# 2_1.net
KiCad netlist of a schematic drawn in EasyEDA Pro
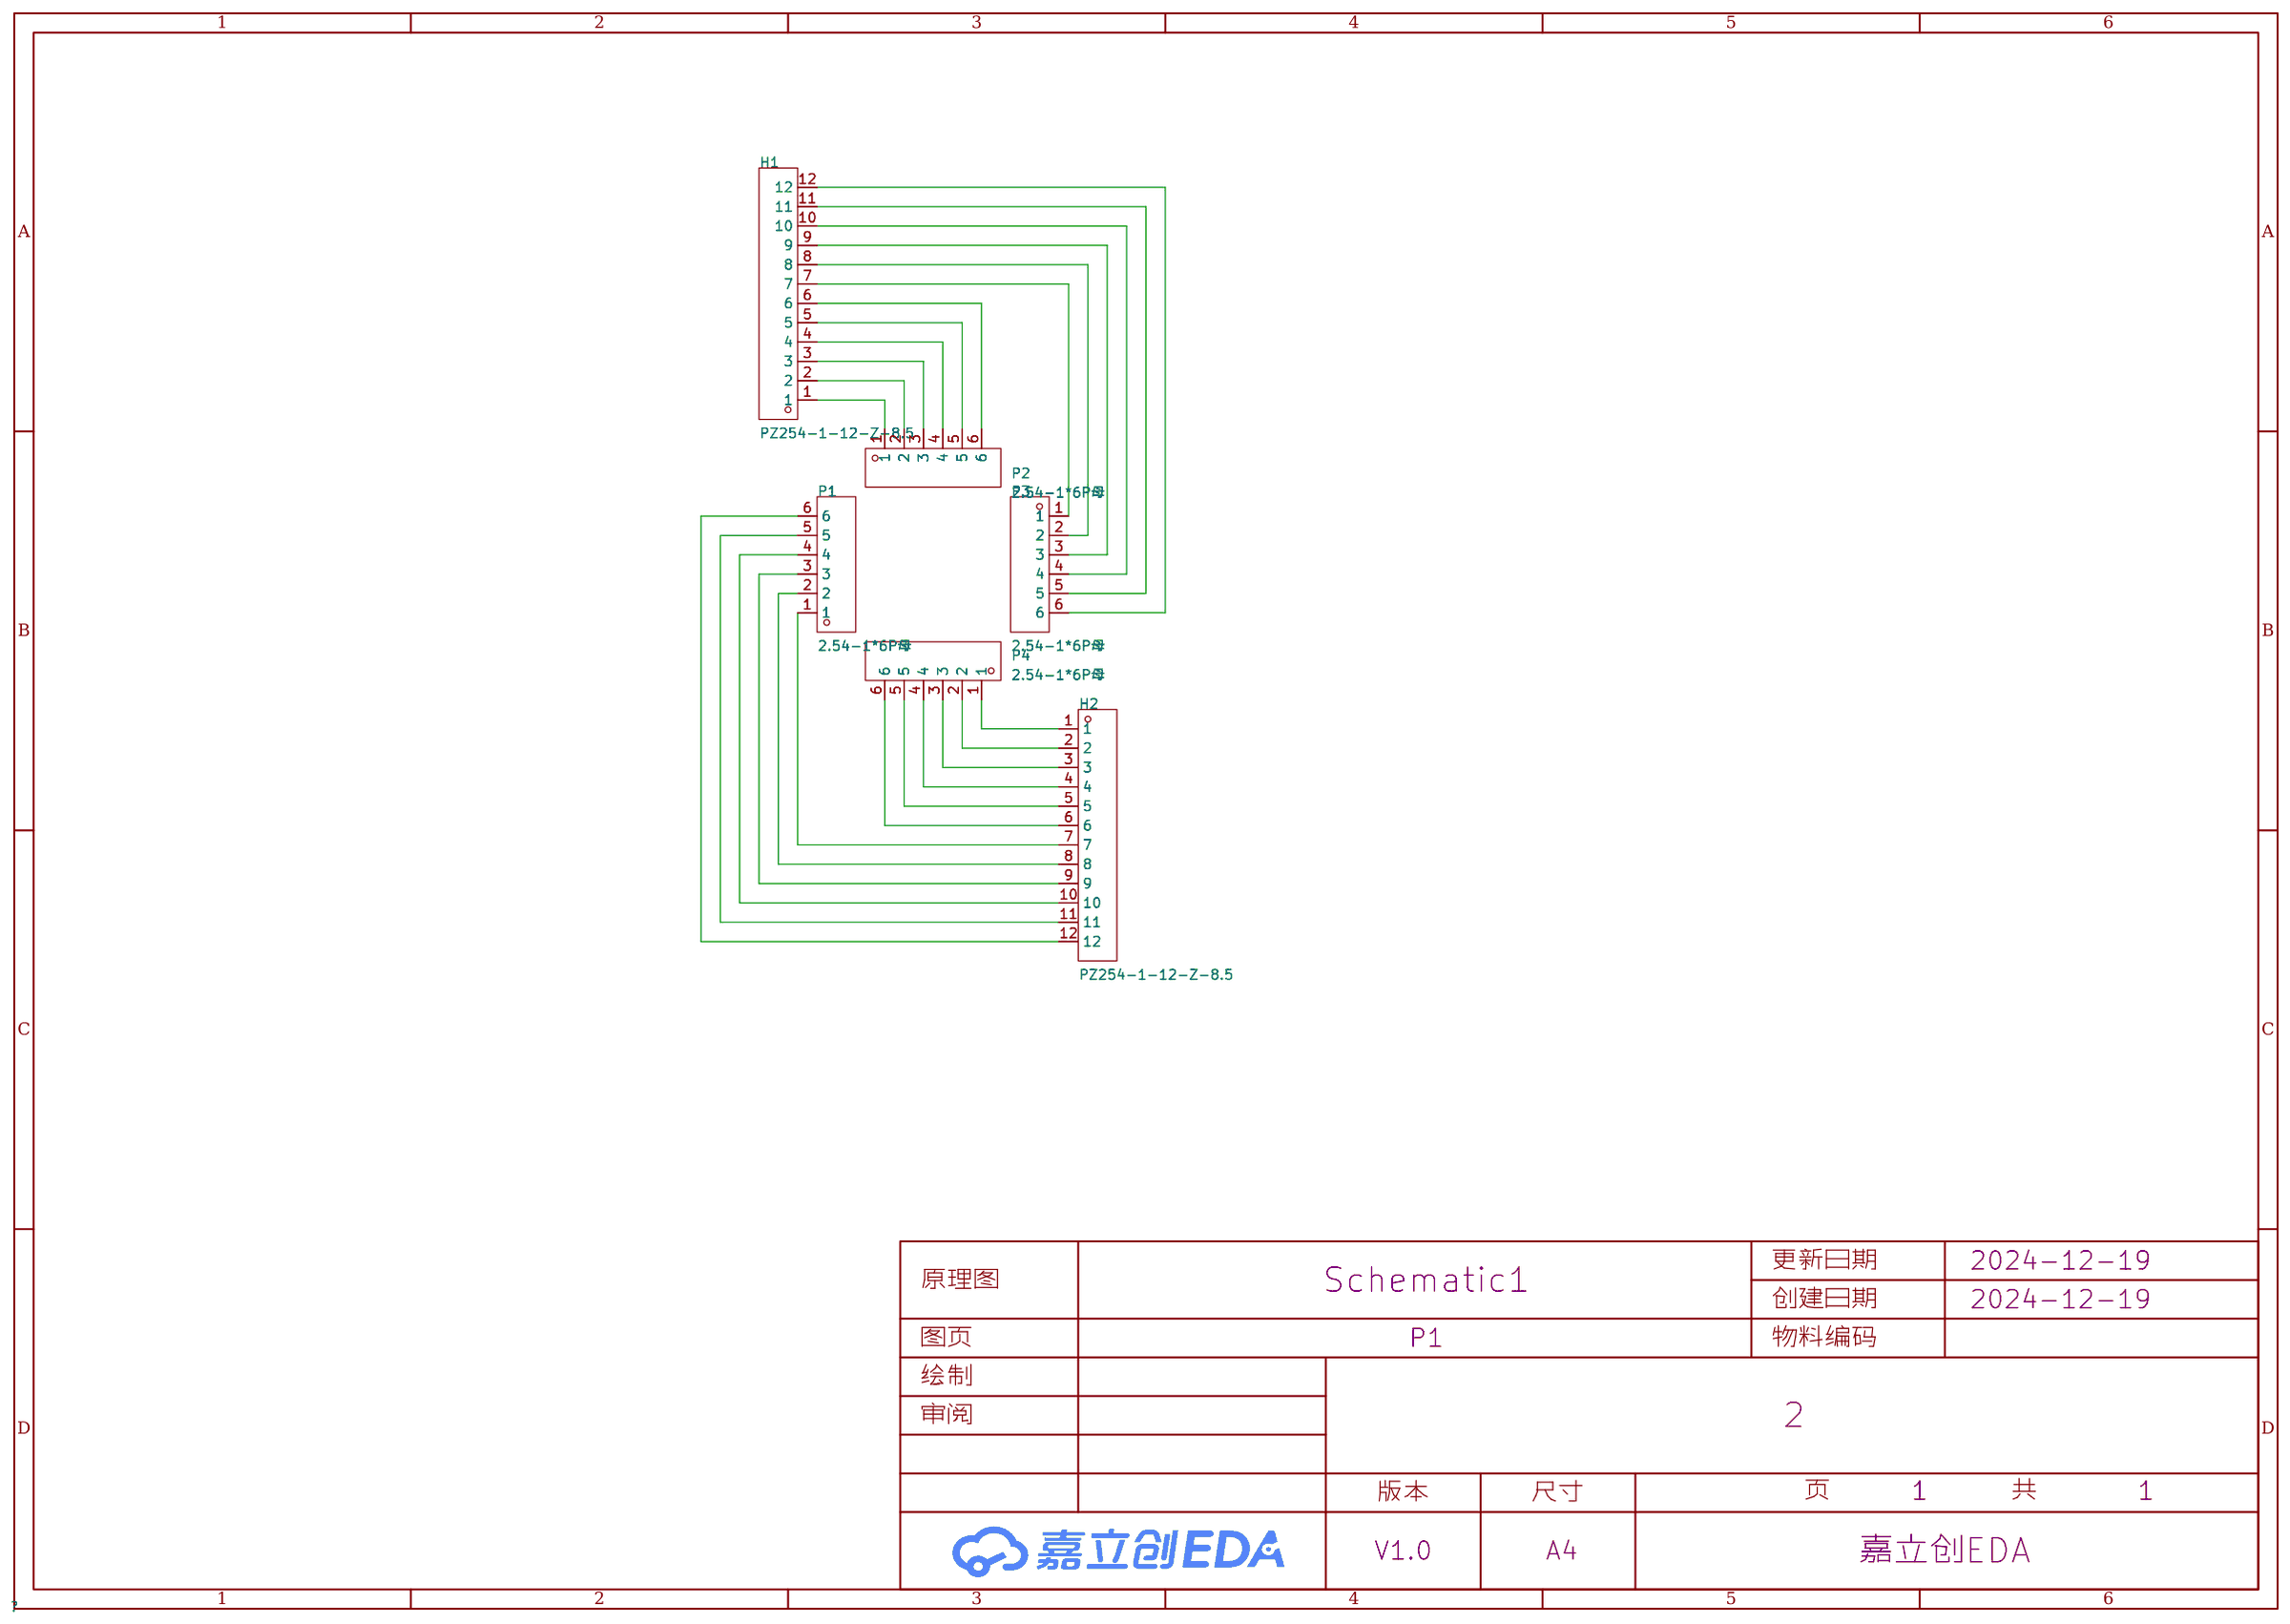
[diagram p0: schematic sheet]

(export (version "E")
  (design (tool "Eeschema 10.0.6"))
  (components
    (comp (ref "H1")
      (value "PZ254-1-12-Z-8.5")
      (footprint "easyedapro:HDR-TH_12P-P2.54-V-M")
      (fields (field (name "Manufacturer") "HCTL(华灿天禄)"))
      (libsource (lib "easyedapro") (part "PZ254-1-12-Z-8.5"))
    )
    (comp (ref "H2")
      (value "PZ254-1-12-Z-8.5")
      (footprint "easyedapro:HDR-TH_12P-P2.54-V-M")
      (fields (field (name "Manufacturer") "HCTL(华灿天禄)"))
      (libsource (lib "easyedapro") (part "PZ254-1-12-Z-8.5"))
    )
    (comp (ref "P1")
      (value "2.54-1*6P母")
      (footprint "easyedapro:HDR-TH_6P-P2.54-V-F")
      (description "插孔结构:1x6P;间距:2.54mm;行距:-;安装类型:直插;排数:单排;总孔位数:6P;塑高:-;触头材质:-;触头镀层:-;")
      (fields (field (name "Manufacturer") "BOOMELE(博穆精密)"))
      (libsource (lib "easyedapro") (part "Header-Female-2.54_1x6"))
    )
    (comp (ref "P2")
      (value "2.54-1*6P母")
      (footprint "easyedapro:HDR-TH_6P-P2.54-V-F")
      (description "插孔结构:1x6P;间距:2.54mm;行距:-;安装类型:直插;排数:单排;总孔位数:6P;塑高:-;触头材质:-;触头镀层:-;")
      (fields (field (name "Manufacturer") "BOOMELE(博穆精密)"))
      (libsource (lib "easyedapro") (part "Header-Female-2.54_1x6"))
    )
    (comp (ref "P3")
      (value "2.54-1*6P母")
      (footprint "easyedapro:HDR-TH_6P-P2.54-V-F")
      (description "插孔结构:1x6P;间距:2.54mm;行距:-;安装类型:直插;排数:单排;总孔位数:6P;塑高:-;触头材质:-;触头镀层:-;")
      (fields (field (name "Manufacturer") "BOOMELE(博穆精密)"))
      (libsource (lib "easyedapro") (part "Header-Female-2.54_1x6"))
    )
    (comp (ref "P4")
      (value "2.54-1*6P母")
      (footprint "easyedapro:HDR-TH_6P-P2.54-V-F")
      (description "插孔结构:1x6P;间距:2.54mm;行距:-;安装类型:直插;排数:单排;总孔位数:6P;塑高:-;触头材质:-;触头镀层:-;")
      (fields (field (name "Manufacturer") "BOOMELE(博穆精密)"))
      (libsource (lib "easyedapro") (part "Header-Female-2.54_1x6"))
    )
  )
  (nets
    (net (code "1") (name "Net-(H1-Pad1)") (class "Default")
      (node (ref "H1") (pin "1") (pinfunction "1_1") (pintype "unspecified"))
      (node (ref "P2") (pin "1") (pinfunction "1_1") (pintype "unspecified"))
    )
    (net (code "2") (name "Net-(H1-Pad2)") (class "Default")
      (node (ref "H1") (pin "2") (pinfunction "2_2") (pintype "unspecified"))
      (node (ref "P2") (pin "2") (pinfunction "2_2") (pintype "unspecified"))
    )
    (net (code "3") (name "Net-(H1-Pad3)") (class "Default")
      (node (ref "H1") (pin "3") (pinfunction "3_3") (pintype "unspecified"))
      (node (ref "P2") (pin "3") (pinfunction "3_3") (pintype "unspecified"))
    )
    (net (code "4") (name "Net-(H1-Pad4)") (class "Default")
      (node (ref "H1") (pin "4") (pinfunction "4_4") (pintype "unspecified"))
      (node (ref "P2") (pin "4") (pinfunction "4_4") (pintype "unspecified"))
    )
    (net (code "5") (name "Net-(H1-Pad5)") (class "Default")
      (node (ref "H1") (pin "5") (pinfunction "5_5") (pintype "unspecified"))
      (node (ref "P2") (pin "5") (pinfunction "5_5") (pintype "unspecified"))
    )
    (net (code "6") (name "Net-(H1-Pad6)") (class "Default")
      (node (ref "H1") (pin "6") (pinfunction "6_6") (pintype "unspecified"))
      (node (ref "P2") (pin "6") (pinfunction "6_6") (pintype "unspecified"))
    )
    (net (code "7") (name "Net-(H1-Pad7)") (class "Default")
      (node (ref "H1") (pin "7") (pinfunction "7_7") (pintype "unspecified"))
      (node (ref "P3") (pin "1") (pinfunction "1_1") (pintype "unspecified"))
    )
    (net (code "8") (name "Net-(H1-Pad8)") (class "Default")
      (node (ref "H1") (pin "8") (pinfunction "8_8") (pintype "unspecified"))
      (node (ref "P3") (pin "2") (pinfunction "2_2") (pintype "unspecified"))
    )
    (net (code "9") (name "Net-(H1-Pad9)") (class "Default")
      (node (ref "H1") (pin "9") (pinfunction "9_9") (pintype "unspecified"))
      (node (ref "P3") (pin "3") (pinfunction "3_3") (pintype "unspecified"))
    )
    (net (code "10") (name "Net-(H1-Pad10)") (class "Default")
      (node (ref "H1") (pin "10") (pinfunction "10_10") (pintype "unspecified"))
      (node (ref "P3") (pin "4") (pinfunction "4_4") (pintype "unspecified"))
    )
    (net (code "11") (name "Net-(H1-Pad11)") (class "Default")
      (node (ref "H1") (pin "11") (pinfunction "11_11") (pintype "unspecified"))
      (node (ref "P3") (pin "5") (pinfunction "5_5") (pintype "unspecified"))
    )
    (net (code "12") (name "Net-(H1-Pad12)") (class "Default")
      (node (ref "H1") (pin "12") (pinfunction "12_12") (pintype "unspecified"))
      (node (ref "P3") (pin "6") (pinfunction "6_6") (pintype "unspecified"))
    )
    (net (code "13") (name "Net-(H2-Pad1)") (class "Default")
      (node (ref "H2") (pin "1") (pinfunction "1_1") (pintype "unspecified"))
      (node (ref "P4") (pin "1") (pinfunction "1_1") (pintype "unspecified"))
    )
    (net (code "14") (name "Net-(H2-Pad2)") (class "Default")
      (node (ref "H2") (pin "2") (pinfunction "2_2") (pintype "unspecified"))
      (node (ref "P4") (pin "2") (pinfunction "2_2") (pintype "unspecified"))
    )
    (net (code "15") (name "Net-(H2-Pad3)") (class "Default")
      (node (ref "H2") (pin "3") (pinfunction "3_3") (pintype "unspecified"))
      (node (ref "P4") (pin "3") (pinfunction "3_3") (pintype "unspecified"))
    )
    (net (code "16") (name "Net-(H2-Pad4)") (class "Default")
      (node (ref "H2") (pin "4") (pinfunction "4_4") (pintype "unspecified"))
      (node (ref "P4") (pin "4") (pinfunction "4_4") (pintype "unspecified"))
    )
    (net (code "17") (name "Net-(H2-Pad5)") (class "Default")
      (node (ref "H2") (pin "5") (pinfunction "5_5") (pintype "unspecified"))
      (node (ref "P4") (pin "5") (pinfunction "5_5") (pintype "unspecified"))
    )
    (net (code "18") (name "Net-(H2-Pad6)") (class "Default")
      (node (ref "H2") (pin "6") (pinfunction "6_6") (pintype "unspecified"))
      (node (ref "P4") (pin "6") (pinfunction "6_6") (pintype "unspecified"))
    )
    (net (code "19") (name "Net-(H2-Pad7)") (class "Default")
      (node (ref "H2") (pin "7") (pinfunction "7_7") (pintype "unspecified"))
      (node (ref "P1") (pin "1") (pinfunction "1_1") (pintype "unspecified"))
    )
    (net (code "20") (name "Net-(H2-Pad8)") (class "Default")
      (node (ref "H2") (pin "8") (pinfunction "8_8") (pintype "unspecified"))
      (node (ref "P1") (pin "2") (pinfunction "2_2") (pintype "unspecified"))
    )
    (net (code "21") (name "Net-(H2-Pad9)") (class "Default")
      (node (ref "H2") (pin "9") (pinfunction "9_9") (pintype "unspecified"))
      (node (ref "P1") (pin "3") (pinfunction "3_3") (pintype "unspecified"))
    )
    (net (code "22") (name "Net-(H2-Pad10)") (class "Default")
      (node (ref "H2") (pin "10") (pinfunction "10_10") (pintype "unspecified"))
      (node (ref "P1") (pin "4") (pinfunction "4_4") (pintype "unspecified"))
    )
    (net (code "23") (name "Net-(H2-Pad11)") (class "Default")
      (node (ref "H2") (pin "11") (pinfunction "11_11") (pintype "unspecified"))
      (node (ref "P1") (pin "5") (pinfunction "5_5") (pintype "unspecified"))
    )
    (net (code "24") (name "Net-(H2-Pad12)") (class "Default")
      (node (ref "H2") (pin "12") (pinfunction "12_12") (pintype "unspecified"))
      (node (ref "P1") (pin "6") (pinfunction "6_6") (pintype "unspecified"))
    )
  )
)
